# tradfri_ICC-1.net
KiCad netlist of a schematic drawn in EAGLE
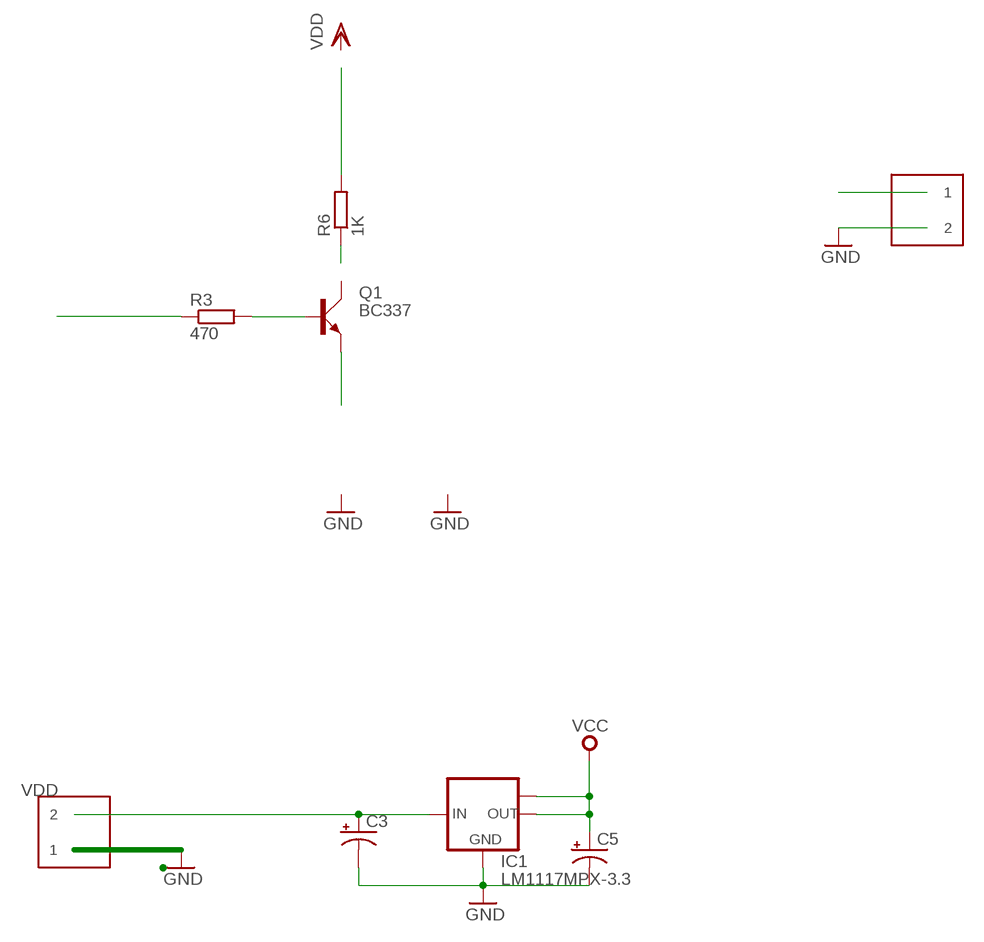
[diagram p0: schematic, sheet 1]

(export (version "E")
  (design (tool "Eeschema 10.0.6"))
  (components
    (comp (ref "C3")
      (value "100UF-25V-20%(PTH)")
      (footprint "eagle-import:CPOL-RADIAL-100UF-25V")
      (libsource (lib "eagle-import") (part "100UF-25V-20%(PTH)"))
    )
    (comp (ref "C5")
      (value "100UF-25V-20%(PTH)")
      (footprint "eagle-import:CPOL-RADIAL-100UF-25V")
      (libsource (lib "eagle-import") (part "100UF-25V-20%(PTH)"))
    )
    (comp (ref "IC1")
      (value "LM1117MPX-3.3")
      (footprint "eagle-import:SOT223")
      (libsource (lib "eagle-import") (part "LM1117MPX-3.3"))
    )
    (comp (ref "PWR_IN")
      (value "KF350-P2")
      (footprint "eagle-import:KF350-2P")
      (libsource (lib "eagle-import") (part "KF350-P2"))
    )
    (comp (ref "Q1")
      (value "BC337")
      (footprint "eagle-import:SOT54A")
      (libsource (lib "eagle-import") (part "BC337"))
    )
    (comp (ref "R3")
      (value "470")
      (footprint "eagle-import:R0805")
      (libsource (lib "eagle-import") (part "R-EU_R0805"))
    )
    (comp (ref "R6")
      (value "1K")
      (footprint "eagle-import:R0805")
      (libsource (lib "eagle-import") (part "R-EU_R0805"))
    )
    (comp (ref "U$3")
      (value "KF350-P2")
      (footprint "eagle-import:KF350-2P")
      (libsource (lib "eagle-import") (part "KF350-P2"))
    )
  )
  (nets
    (net (code "1") (name "GND") (class "Default")
      (node (ref "C3") (pin "2") (pinfunction "-_2") (pintype "passive"))
      (node (ref "C5") (pin "2") (pinfunction "-_2") (pintype "passive"))
      (node (ref "IC1") (pin "1") (pinfunction "GND_1") (pintype "input"))
      (node (ref "PWR_IN") (pin "1") (pinfunction "1_1") (pintype "bidirectional"))
      (node (ref "U$3") (pin "2") (pinfunction "2_2") (pintype "bidirectional"))
    )
    (net (code "2") (name "Net-(Q1-PadB)") (class "Default")
      (node (ref "Q1") (pin "B") (pinfunction "B_B") (pintype "passive"))
      (node (ref "R3") (pin "2") (pinfunction "2_2") (pintype "passive"))
    )
    (net (code "3") (name "VCC") (class "Default")
      (node (ref "C5") (pin "1") (pinfunction "+_1") (pintype "passive"))
      (node (ref "IC1") (pin "2") (pinfunction "OUT_2") (pintype "passive"))
      (node (ref "IC1") (pin "TAB") (pinfunction "OUT1_TAB") (pintype "passive"))
    )
    (net (code "4") (name "VDD") (class "Default")
      (node (ref "C3") (pin "1") (pinfunction "+_1") (pintype "passive"))
      (node (ref "IC1") (pin "3") (pinfunction "IN_3") (pintype "input"))
      (node (ref "PWR_IN") (pin "2") (pinfunction "2_2") (pintype "bidirectional"))
      (node (ref "R6") (pin "2") (pinfunction "2_2") (pintype "passive"))
    )
    (net (code "5") (name "unconnected-(Q1-PadC)") (class "Default")
      (node (ref "Q1") (pin "C") (pinfunction "C_C") (pintype "passive"))
    )
    (net (code "6") (name "unconnected-(Q1-PadE)") (class "Default")
      (node (ref "Q1") (pin "E") (pinfunction "E_E") (pintype "passive"))
    )
    (net (code "7") (name "unconnected-(R3-Pad1)") (class "Default")
      (node (ref "R3") (pin "1") (pinfunction "1_1") (pintype "passive"))
    )
    (net (code "8") (name "unconnected-(R6-Pad1)") (class "Default")
      (node (ref "R6") (pin "1") (pinfunction "1_1") (pintype "passive"))
    )
    (net (code "9") (name "unconnected-(U$3-Pad1)") (class "Default")
      (node (ref "U$3") (pin "1") (pinfunction "1_1") (pintype "bidirectional"))
    )
  )
)
